# eLight_pro.net
KiCad netlist of a schematic drawn in EasyEDA Pro
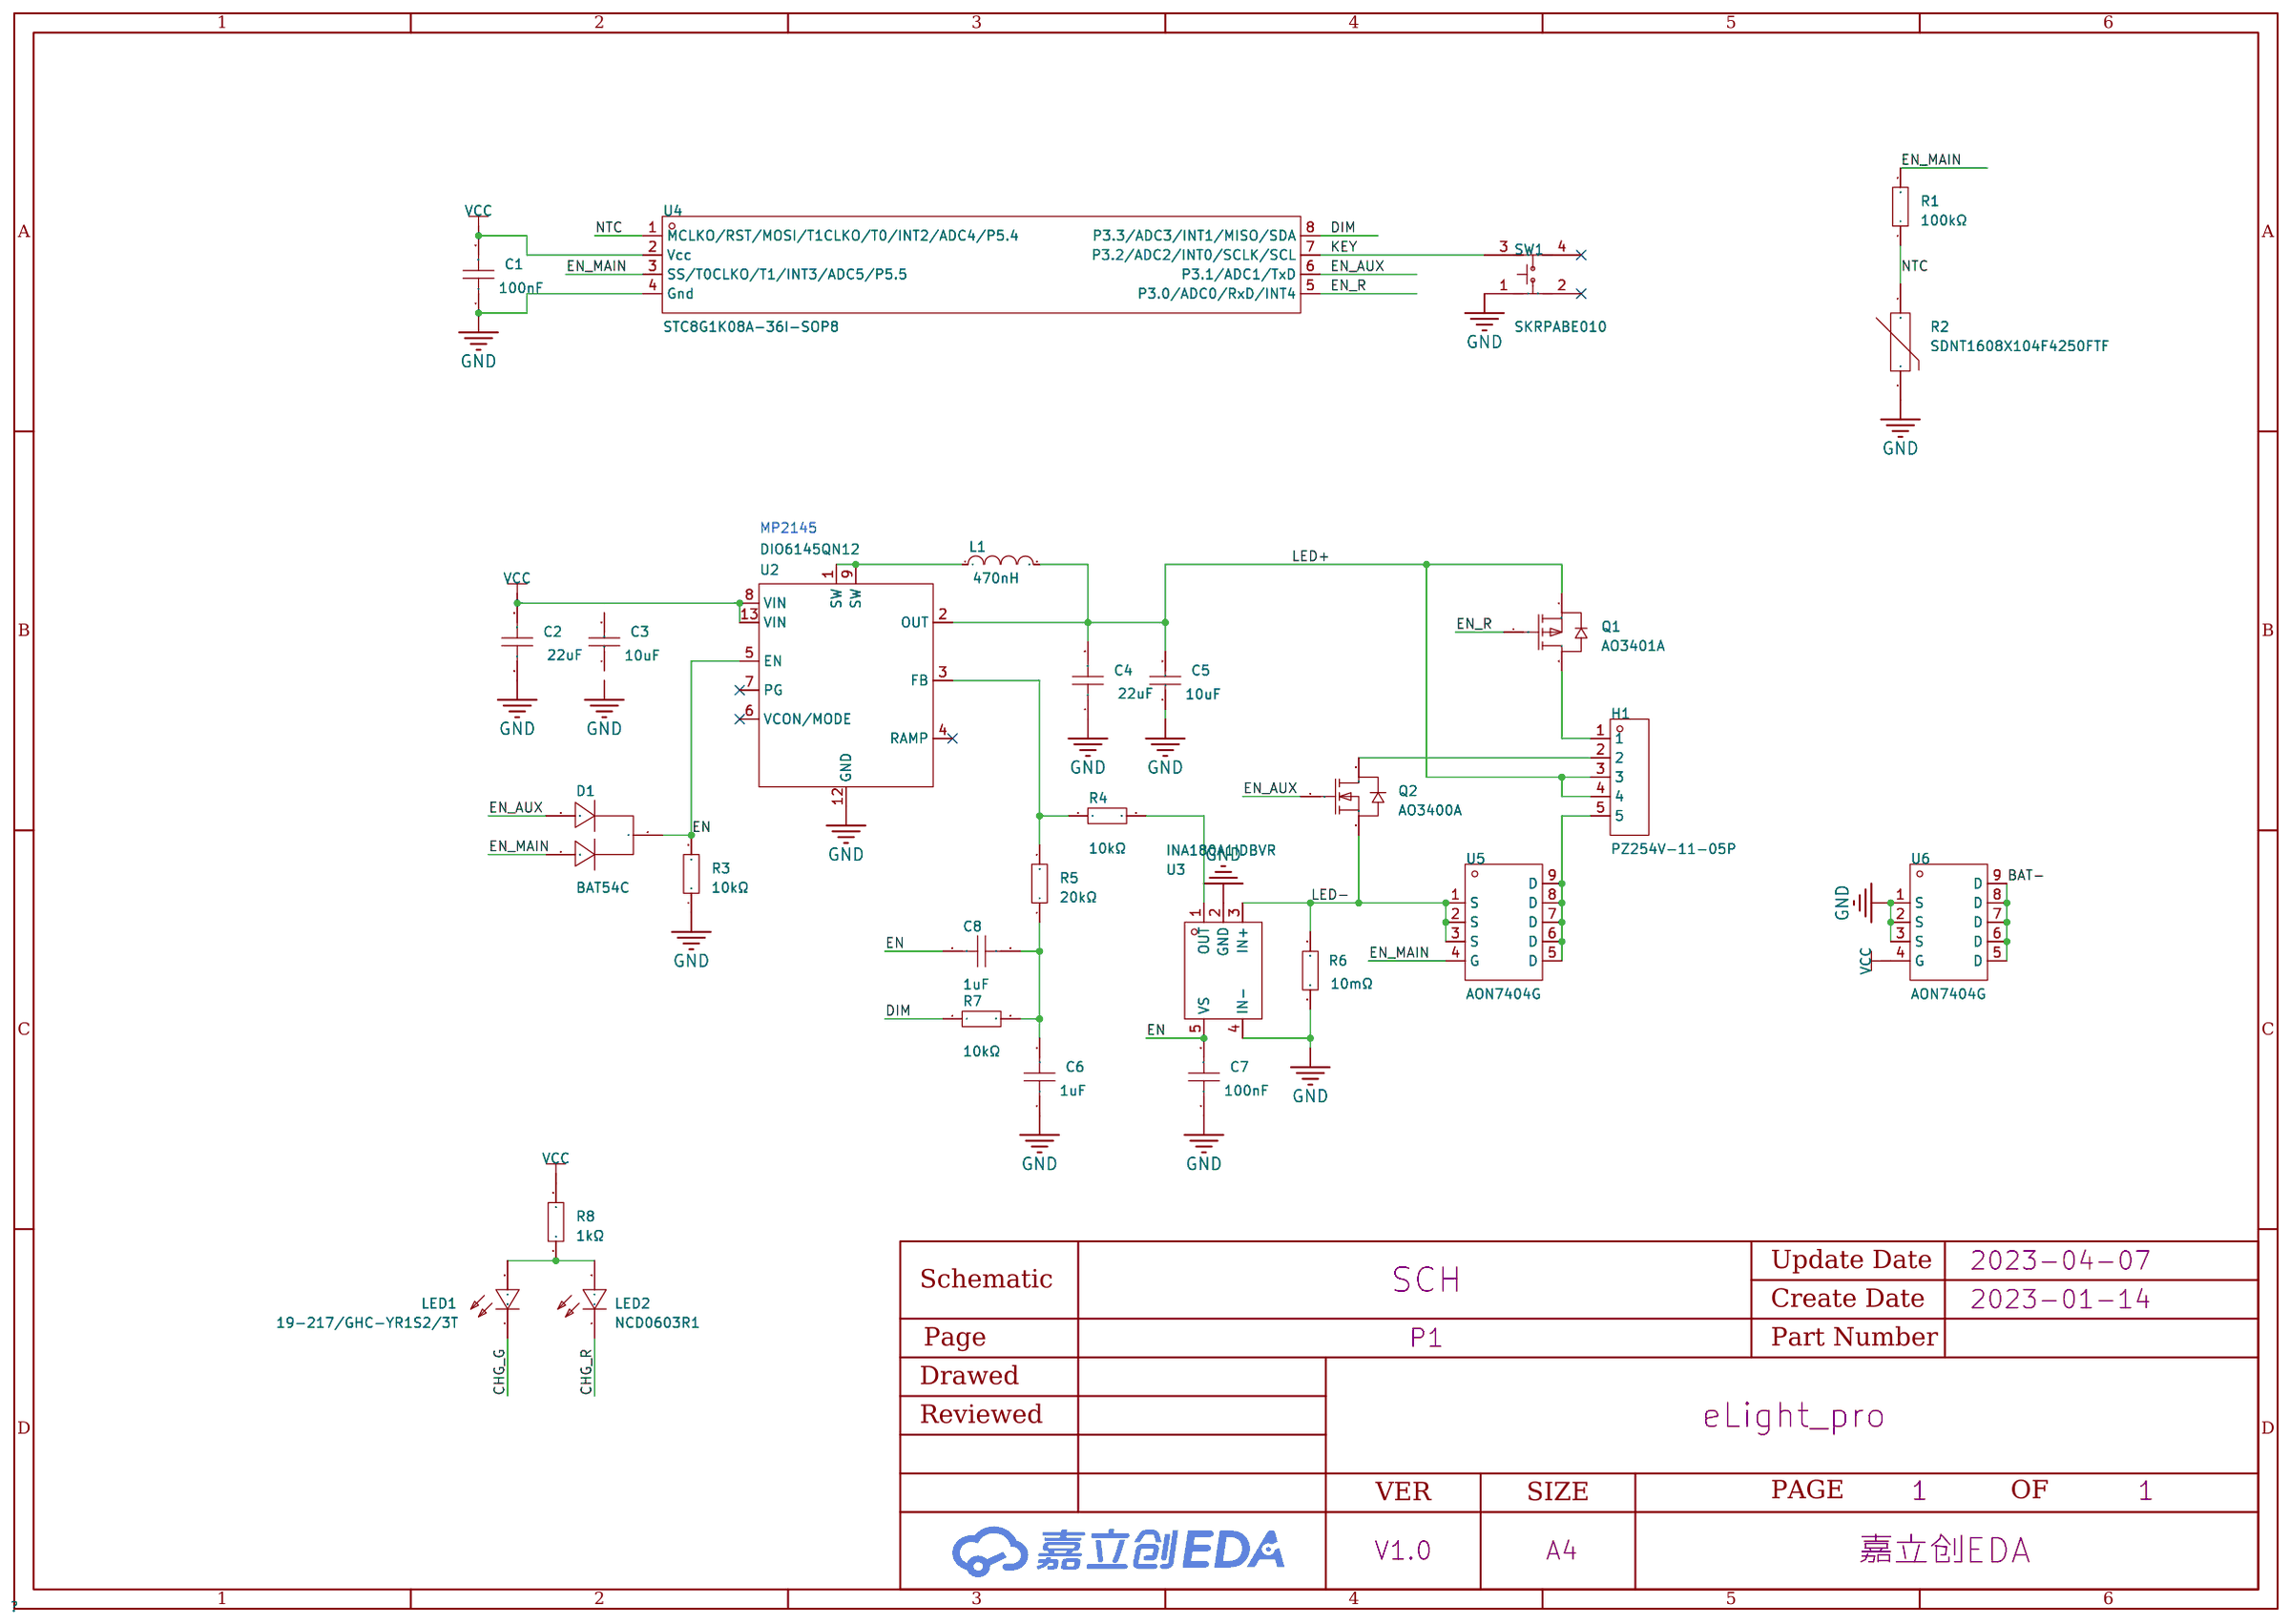
[diagram p0: schematic sheet]

(export (version "E")
  (design (tool "Eeschema 10.0.6"))
  (components
    (comp (ref "C1")
      (value "100nF")
      (footprint "easyedapro:C0603")
      (description "容值:100nF;精度:±10%;额定电压:50V;材质(温度系数):X7R;")
      (fields
        (field (name "Manufacturer Part") "CC0603KRX7R9BB104")
        (field (name "Manufacturer") "YAGEO(国巨)")
      )
      (libsource (lib "easyedapro") (part "CC0603KRX7R9BB104"))
    )
    (comp (ref "C2")
      (value "22uF")
      (footprint "easyedapro:C0805")
      (description "容值:22uF;精度:±20%;额定电压:25V;材质(温度系数):X5R;")
      (fields
        (field (name "Manufacturer Part") "CL21A226MAQNNNE")
        (field (name "Manufacturer") "SAMSUNG(三星)")
      )
      (libsource (lib "easyedapro") (part "CL21A226MAQNNNE"))
    )
    (comp (ref "C3")
      (value "10uF")
      (footprint "easyedapro:C0603")
      (description "容值:1uF;精度:±10%;额定电压:50V;材质(温度系数):X5R;")
      (fields
        (field (name "Manufacturer Part") "CL10A106KP8NNNC")
        (field (name "Manufacturer") "SAMSUNG(三星)")
      )
      (libsource (lib "easyedapro") (part "CL10A105KB8NNNC"))
    )
    (comp (ref "C4")
      (value "22uF")
      (footprint "easyedapro:C0805")
      (description "容值:22uF;精度:±20%;额定电压:25V;材质(温度系数):X5R;")
      (fields
        (field (name "Manufacturer Part") "CL21A226MAQNNNE")
        (field (name "Manufacturer") "SAMSUNG(三星)")
      )
      (libsource (lib "easyedapro") (part "CL21A226MAQNNNE"))
    )
    (comp (ref "C5")
      (value "10uF")
      (footprint "easyedapro:C0603")
      (description "容值:1uF;精度:±10%;额定电压:50V;材质(温度系数):X5R;")
      (fields
        (field (name "Manufacturer Part") "CL10A106KP8NNNC")
        (field (name "Manufacturer") "SAMSUNG(三星)")
      )
      (libsource (lib "easyedapro") (part "CL10A105KB8NNNC"))
    )
    (comp (ref "C6")
      (value "1uF")
      (footprint "easyedapro:C0603")
      (description "温度系数:X5R;精度:±10%;额定电压:50V;容值:1uF;")
      (fields
        (field (name "Manufacturer Part") "CL10A105KB8NNNC")
        (field (name "Manufacturer") "SAMSUNG(三星)")
      )
      (libsource (lib "easyedapro") (part "CL10A106KP8NNNC"))
    )
    (comp (ref "C7")
      (value "100nF")
      (footprint "easyedapro:C0603")
      (description "容值:100nF;精度:±10%;额定电压:50V;材质(温度系数):X7R;")
      (fields
        (field (name "Manufacturer Part") "CC0603KRX7R9BB104")
        (field (name "Manufacturer") "YAGEO(国巨)")
      )
      (libsource (lib "easyedapro") (part "CC0603KRX7R9BB104"))
    )
    (comp (ref "C8")
      (value "1uF")
      (footprint "easyedapro:C0603")
      (description "温度系数:X5R;精度:±10%;额定电压:50V;容值:1uF;")
      (fields
        (field (name "Manufacturer Part") "CL10A105KB8NNNC")
        (field (name "Manufacturer") "SAMSUNG(三星)")
      )
      (libsource (lib "easyedapro") (part "CL10A106KP8NNNC"))
    )
    (comp (ref "D1")
      (value "BAT54C")
      (footprint "easyedapro:SOT-23-3_L2.9-W1.6-P1.90-LS2.8-BR")
      (description "二极管配置:-;直流反向耐压(Vr):30V;平均整流电流(Io):200mA;正向压降(Vf):1V@100mA;反向电流(Ir):-;")
      (fields (field (name "Manufacturer") "CJ(江苏长电/长晶)"))
      (libsource (lib "easyedapro") (part "BAT54C"))
    )
    (comp (ref "H1")
      (value "PZ254V-11-05P")
      (footprint "easyedapro:HDR-TH_5P-P2.54-V-M")
      (fields (field (name "Manufacturer") "XFCN(兴飞)"))
      (libsource (lib "easyedapro") (part "PZ254V-11-05P"))
    )
    (comp (ref "L1")
      (value "470nH")
      (footprint "easyedapro:IND-SMD_L4.5-W4.0-1")
      (description "电感值:2.2uH;精度:±20%;额定电流:3A;直流电阻(DCR):52mΩ;")
      (fields (field (name "Manufacturer Part") "FXL0420-R47-M") (field (name "Manufacturer") "cjiang(长江微电)"))
      (libsource (lib "easyedapro") (part "MCS0420-2R2MN2"))
    )
    (comp (ref "LED1")
      (value "19-217/GHC-YR1S2/3T")
      (footprint "easyedapro:LED0603-RD")
      (fields (field (name "Manufacturer") "EVERLIGHT(亿光)"))
      (libsource (lib "easyedapro") (part "19-217/GHC-YR1S2/3T"))
    )
    (comp (ref "LED2")
      (value "NCD0603R1")
      (footprint "easyedapro:LED0603-RD_RED")
      (description "发光颜色:红灯;")
      (fields (field (name "Manufacturer") "国星光电"))
      (libsource (lib "easyedapro") (part "FC-DA1608HRK-620D"))
    )
    (comp (ref "Q1")
      (value "AO3401A")
      (footprint "easyedapro:SOT-23_L2.9-W1.3-P1.90-LS2.4-BR")
      (fields (field (name "Manufacturer") "AOS"))
      (libsource (lib "easyedapro") (part "AO3401A"))
    )
    (comp (ref "Q2")
      (value "AO3400A")
      (footprint "easyedapro:SOT-23-3_L2.9-W1.6-P1.90-LS2.8-BR")
      (fields (field (name "Manufacturer") "AOS"))
      (libsource (lib "easyedapro") (part "AO3400A"))
    )
    (comp (ref "R1")
      (value "100kΩ")
      (footprint "easyedapro:R0603")
      (description "电阻类型:厚膜电阻;阻值:10kΩ;精度:±1%;功率:100mW;温度系数:±100ppm/°C;最大工作电压:75V;工作温度范围:-55°C~+155°C;")
      (fields
        (field (name "Manufacturer Part") "0603WAF1003T5E")
        (field (name "Manufacturer") "UNI-ROYAL(厚声)")
      )
      (libsource (lib "easyedapro") (part "0603WAF1002T5E"))
    )
    (comp (ref "R2")
      (value "SDNT1608X104F4250FTF")
      (footprint "easyedapro:R0603")
      (fields (field (name "Manufacturer") "Sunlord(顺络)"))
      (libsource (lib "easyedapro") (part "SDNT1608X103F3950FTF"))
    )
    (comp (ref "R3")
      (value "10kΩ")
      (footprint "easyedapro:R0603")
      (description "电阻类型:厚膜电阻;阻值:100kΩ;精度:±1%;功率:100mW;温度系数:±100ppm/°C;最大工作电压:75V;工作温度范围:-55°C~+155°C;")
      (fields
        (field (name "Manufacturer Part") "0603WAF1002T5E")
        (field (name "Manufacturer") "UNI-ROYAL(厚声)")
      )
      (libsource (lib "easyedapro") (part "0603WAF1003T5E"))
    )
    (comp (ref "R4")
      (value "10kΩ")
      (footprint "easyedapro:R0603")
      (description "电阻类型:厚膜电阻;阻值:100kΩ;精度:±1%;功率:100mW;温度系数:±100ppm/°C;最大工作电压:75V;工作温度范围:-55°C~+155°C;")
      (fields
        (field (name "Manufacturer Part") "0603WAF1002T5E")
        (field (name "Manufacturer") "UNI-ROYAL(厚声)")
      )
      (libsource (lib "easyedapro") (part "0603WAF1003T5E"))
    )
    (comp (ref "R5")
      (value "20kΩ")
      (footprint "easyedapro:R0603")
      (description "电阻类型:厚膜电阻;阻值:100kΩ;精度:±1%;功率:100mW;温度系数:±100ppm/°C;最大工作电压:75V;工作温度范围:-55°C~+155°C;")
      (fields
        (field (name "Manufacturer Part") "0603WAF2002T5E")
        (field (name "Manufacturer") "UNI-ROYAL(厚声)")
      )
      (libsource (lib "easyedapro") (part "0603WAF1003T5E"))
    )
    (comp (ref "R6")
      (value "10mΩ")
      (footprint "easyedapro:R1206")
      (description "阻值:10mΩ;精度:±1%;功率:1W;温度系数:±70ppm/°C;")
      (fields (field (name "Manufacturer Part") "FMF06FTHR010-LH") (field (name "Manufacturer") "PSA(信昌电陶)"))
      (libsource (lib "easyedapro") (part "FMF06FTHR010-LHL"))
    )
    (comp (ref "R7")
      (value "10kΩ")
      (footprint "easyedapro:R0603")
      (description "电阻类型:厚膜电阻;阻值:100kΩ;精度:±1%;功率:100mW;温度系数:±100ppm/°C;最大工作电压:75V;工作温度范围:-55°C~+155°C;")
      (fields
        (field (name "Manufacturer Part") "0603WAF1002T5E")
        (field (name "Manufacturer") "UNI-ROYAL(厚声)")
      )
      (libsource (lib "easyedapro") (part "0603WAF1003T5E"))
    )
    (comp (ref "R8")
      (value "1kΩ")
      (footprint "easyedapro:R0603")
      (description "电阻类型:厚膜电阻;阻值:1kΩ;精度:±1%;功率:100mW;温度系数:±100ppm/°C;最大工作电压:75V;工作温度范围:-55°C~+155°C;")
      (fields
        (field (name "Manufacturer Part") "0603WAF1001T5E")
        (field (name "Manufacturer") "UNI-ROYAL(厚声)")
      )
      (libsource (lib "easyedapro") (part "0603WAF1001T5E"))
    )
    (comp (ref "SW1")
      (value "SKRPABE010")
      (footprint "easyedapro:KEY-SMD_4P-L4.2-W3.2-P2.20-LS4.6")
      (description "触点电流:50mA;额定电压(DC):16V;电路结构:单刀单掷;按钮作用方向:顶部触动;致动器样式:椭圆形按钮;照明颜色:-;开关长度:4.2mm;开关宽度:3.2mm;开关高度:2.5mm;")
      (fields (field (name "Manufacturer") "ALPSALPINE(阿尔卑斯阿尔派)"))
      (libsource (lib "easyedapro") (part "SKRPABE010"))
    )
    (comp (ref "U2")
      (value "DIO6145QN12")
      (footprint "easyedapro:QFN-12_L3.0-W2.0-P0.50_DIO6145QN12")
      (fields (field (name "Manufacturer") "DIOO(帝奥微)"))
      (libsource (lib "easyedapro") (part "DIO6145QN12"))
    )
    (comp (ref "U3")
      (value "INA180A1IDBVR")
      (footprint "easyedapro:SOT-23-5_L3.0-W1.7-P0.95-LS2.8-BR")
      (description "INA180 INA180 多通道电流感应放大器")
      (fields (field (name "Manufacturer") "TI(德州仪器)"))
      (libsource (lib "easyedapro") (part "INA180A1IDBVR"))
    )
    (comp (ref "U4")
      (value "STC8G1K08A-36I-SOP8")
      (footprint "easyedapro:SOP-8_L5.0-W4.0-P1.27-LS6.0-BL")
      (fields (field (name "Manufacturer") "STC(宏晶)"))
      (libsource (lib "easyedapro") (part "STC8G1K08A-36I-SOP8"))
    )
    (comp (ref "U5")
      (value "AON7404G")
      (footprint "easyedapro:DFN-8_L3.0-W3.0-P0.65-BL-2")
      (fields (field (name "Manufacturer") "AOS"))
      (libsource (lib "easyedapro") (part "AON7404G"))
    )
    (comp (ref "U6")
      (value "AON7404G")
      (footprint "easyedapro:DFN-8_L3.0-W3.0-P0.65-BL-2")
      (fields (field (name "Manufacturer") "AOS"))
      (libsource (lib "easyedapro") (part "AON7404G"))
    )
  )
  (nets
    (net (code "1") (name "/BAT-") (class "Default")
      (node (ref "U6") (pin "5") (pinfunction "D_5") (pintype "input"))
      (node (ref "U6") (pin "6") (pinfunction "D_6") (pintype "input"))
      (node (ref "U6") (pin "7") (pinfunction "D_7") (pintype "input"))
      (node (ref "U6") (pin "8") (pinfunction "D_8") (pintype "input"))
      (node (ref "U6") (pin "9") (pinfunction "D_9") (pintype "input"))
    )
    (net (code "2") (name "/CHG_G") (class "Default")
      (node (ref "LED1") (pin "1") (pinfunction "C_1") (pintype "input"))
    )
    (net (code "3") (name "/CHG_R") (class "Default")
      (node (ref "LED2") (pin "1") (pinfunction "K_1") (pintype "input"))
    )
    (net (code "4") (name "/DIM") (class "Default")
      (node (ref "R7") (pin "1") (pinfunction "1_1") (pintype "input"))
      (node (ref "U4") (pin "8") (pinfunction "P3.3/ADC3/INT1/MISO/SDA_8") (pintype "input"))
    )
    (net (code "5") (name "/EN") (class "Default")
      (node (ref "C7") (pin "2") (pinfunction "2_2") (pintype "input"))
      (node (ref "C8") (pin "2") (pinfunction "2_2") (pintype "input"))
      (node (ref "D1") (pin "3") (pinfunction "K_3") (pintype "input"))
      (node (ref "R3") (pin "2") (pinfunction "2_2") (pintype "input"))
      (node (ref "U2") (pin "5") (pinfunction "EN_5") (pintype "input"))
      (node (ref "U3") (pin "5") (pinfunction "VS_5") (pintype "input"))
    )
    (net (code "6") (name "/EN_AUX") (class "Default")
      (node (ref "D1") (pin "1") (pinfunction "A1_1") (pintype "input"))
      (node (ref "Q2") (pin "1") (pinfunction "G_1") (pintype "input"))
      (node (ref "U4") (pin "6") (pinfunction "P3.1/ADC1/TxD_6") (pintype "input"))
    )
    (net (code "7") (name "/EN_MAIN") (class "Default")
      (node (ref "D1") (pin "2") (pinfunction "A2_2") (pintype "input"))
      (node (ref "R1") (pin "2") (pinfunction "2_2") (pintype "input"))
      (node (ref "U4") (pin "3") (pinfunction "SS/T0CLKO/T1/INT3/ADC5/P5.5_3") (pintype "input"))
      (node (ref "U5") (pin "4") (pinfunction "G_4") (pintype "input"))
    )
    (net (code "8") (name "/EN_R") (class "Default")
      (node (ref "Q1") (pin "1") (pinfunction "G_1") (pintype "input"))
      (node (ref "U4") (pin "5") (pinfunction "P3.0/ADC0/RxD/INT4_5") (pintype "input"))
    )
    (net (code "9") (name "/KEY") (class "Default")
      (node (ref "SW1") (pin "3") (pinfunction "3_3") (pintype "input"))
      (node (ref "U4") (pin "7") (pinfunction "P3.2/ADC2/INT0/SCLK/SCL_7") (pintype "input"))
    )
    (net (code "10") (name "/LED+") (class "Default")
      (node (ref "C4") (pin "2") (pinfunction "2_2") (pintype "input"))
      (node (ref "C5") (pin "2") (pinfunction "2_2") (pintype "input"))
      (node (ref "H1") (pin "3") (pinfunction "3_3") (pintype "input"))
      (node (ref "H1") (pin "4") (pinfunction "4_4") (pintype "input"))
      (node (ref "L1") (pin "2") (pinfunction "2_2") (pintype "input"))
      (node (ref "Q1") (pin "2") (pinfunction "S_2") (pintype "input"))
      (node (ref "U2") (pin "2") (pinfunction "OUT_2") (pintype "input"))
    )
    (net (code "11") (name "/LED-") (class "Default")
      (node (ref "Q2") (pin "2") (pinfunction "S_2") (pintype "input"))
      (node (ref "R6") (pin "2") (pinfunction "2_2") (pintype "input"))
      (node (ref "U3") (pin "3") (pinfunction "IN+_3") (pintype "input"))
      (node (ref "U5") (pin "1") (pinfunction "S_1") (pintype "input"))
      (node (ref "U5") (pin "2") (pinfunction "S_2") (pintype "input"))
      (node (ref "U5") (pin "3") (pinfunction "S_3") (pintype "input"))
    )
    (net (code "12") (name "/NTC") (class "Default")
      (node (ref "R1") (pin "1") (pinfunction "1_1") (pintype "input"))
      (node (ref "R2") (pin "2") (pinfunction "2_2") (pintype "input"))
      (node (ref "U4") (pin "1") (pinfunction "MCLKO/RST/MOSI/T1CLKO/T0/INT2/ADC4/P5.4_1") (pintype "input"))
    )
    (net (code "13") (name "GND") (class "Default")
      (node (ref "C1") (pin "1") (pinfunction "1_1") (pintype "input"))
      (node (ref "C2") (pin "1") (pinfunction "1_1") (pintype "input"))
      (node (ref "C4") (pin "1") (pinfunction "1_1") (pintype "input"))
      (node (ref "C5") (pin "1") (pinfunction "1_1") (pintype "input"))
      (node (ref "C6") (pin "1") (pinfunction "1_1") (pintype "input"))
      (node (ref "C7") (pin "1") (pinfunction "1_1") (pintype "input"))
      (node (ref "R2") (pin "1") (pinfunction "1_1") (pintype "input"))
      (node (ref "R3") (pin "1") (pinfunction "1_1") (pintype "input"))
      (node (ref "R6") (pin "1") (pinfunction "1_1") (pintype "input"))
      (node (ref "SW1") (pin "1") (pinfunction "1_1") (pintype "input"))
      (node (ref "U2") (pin "12") (pinfunction "GND_12") (pintype "input"))
      (node (ref "U3") (pin "2") (pinfunction "GND_2") (pintype "input"))
      (node (ref "U3") (pin "4") (pinfunction "IN-_4") (pintype "input"))
      (node (ref "U4") (pin "4") (pinfunction "Gnd_4") (pintype "input"))
      (node (ref "U6") (pin "1") (pinfunction "S_1") (pintype "input"))
      (node (ref "U6") (pin "2") (pinfunction "S_2") (pintype "input"))
      (node (ref "U6") (pin "3") (pinfunction "S_3") (pintype "input"))
    )
    (net (code "14") (name "Net-(C6-Pad2)") (class "Default")
      (node (ref "C6") (pin "2") (pinfunction "2_2") (pintype "input"))
      (node (ref "C8") (pin "1") (pinfunction "1_1") (pintype "input"))
      (node (ref "R5") (pin "1") (pinfunction "1_1") (pintype "input"))
      (node (ref "R7") (pin "2") (pinfunction "2_2") (pintype "input"))
    )
    (net (code "15") (name "Net-(H1-Pad5)") (class "Default")
      (node (ref "H1") (pin "5") (pinfunction "5_5") (pintype "input"))
      (node (ref "U5") (pin "5") (pinfunction "D_5") (pintype "input"))
      (node (ref "U5") (pin "6") (pinfunction "D_6") (pintype "input"))
      (node (ref "U5") (pin "7") (pinfunction "D_7") (pintype "input"))
      (node (ref "U5") (pin "8") (pinfunction "D_8") (pintype "input"))
      (node (ref "U5") (pin "9") (pinfunction "D_9") (pintype "input"))
    )
    (net (code "16") (name "Net-(L1-Pad1)") (class "Default")
      (node (ref "L1") (pin "1") (pinfunction "1_1") (pintype "input"))
      (node (ref "U2") (pin "1") (pinfunction "SW_1") (pintype "input"))
      (node (ref "U2") (pin "9") (pinfunction "SW_9") (pintype "input"))
    )
    (net (code "17") (name "Net-(LED1-A)") (class "Default")
      (node (ref "LED1") (pin "2") (pinfunction "A_2") (pintype "input"))
      (node (ref "LED2") (pin "2") (pinfunction "A_2") (pintype "input"))
      (node (ref "R8") (pin "1") (pinfunction "1_1") (pintype "input"))
    )
    (net (code "18") (name "Net-(Q1-D)") (class "Default")
      (node (ref "H1") (pin "1") (pinfunction "1_1") (pintype "input"))
      (node (ref "Q1") (pin "3") (pinfunction "D_3") (pintype "input"))
    )
    (net (code "19") (name "Net-(Q2-D)") (class "Default")
      (node (ref "H1") (pin "2") (pinfunction "2_2") (pintype "input"))
      (node (ref "Q2") (pin "3") (pinfunction "D_3") (pintype "input"))
    )
    (net (code "20") (name "Net-(U2-FB)") (class "Default")
      (node (ref "R4") (pin "1") (pinfunction "1_1") (pintype "input"))
      (node (ref "R5") (pin "2") (pinfunction "2_2") (pintype "input"))
      (node (ref "U2") (pin "3") (pinfunction "FB_3") (pintype "input"))
    )
    (net (code "21") (name "Net-(U3-OUT)") (class "Default")
      (node (ref "R4") (pin "2") (pinfunction "2_2") (pintype "input"))
      (node (ref "U3") (pin "1") (pinfunction "OUT_1") (pintype "input"))
    )
    (net (code "22") (name "VCC") (class "Default")
      (node (ref "C1") (pin "2") (pinfunction "2_2") (pintype "input"))
      (node (ref "C2") (pin "2") (pinfunction "2_2") (pintype "input"))
      (node (ref "R8") (pin "2") (pinfunction "2_2") (pintype "input"))
      (node (ref "U2") (pin "13") (pinfunction "VIN_13") (pintype "input"))
      (node (ref "U2") (pin "8") (pinfunction "VIN_8") (pintype "input"))
      (node (ref "U4") (pin "2") (pinfunction "Vcc_2") (pintype "input"))
      (node (ref "U6") (pin "4") (pinfunction "G_4") (pintype "input"))
    )
    (net (code "23") (name "unconnected-(C3-Pad1)") (class "Default")
      (node (ref "C3") (pin "1") (pinfunction "1_1") (pintype "input"))
    )
    (net (code "24") (name "unconnected-(C3-Pad2)") (class "Default")
      (node (ref "C3") (pin "2") (pinfunction "2_2") (pintype "input"))
    )
    (net (code "25") (name "unconnected-(SW1-Pad2)") (class "Default")
      (node (ref "SW1") (pin "2") (pinfunction "2_2") (pintype "input+no_connect"))
    )
    (net (code "26") (name "unconnected-(SW1-Pad4)") (class "Default")
      (node (ref "SW1") (pin "4") (pinfunction "4_4") (pintype "input+no_connect"))
    )
    (net (code "27") (name "unconnected-(U2-PG-Pad7)") (class "Default")
      (node (ref "U2") (pin "7") (pinfunction "PG_7") (pintype "input+no_connect"))
    )
    (net (code "28") (name "unconnected-(U2-RAMP-Pad4)") (class "Default")
      (node (ref "U2") (pin "4") (pinfunction "RAMP_4") (pintype "input+no_connect"))
    )
    (net (code "29") (name "unconnected-(U2-VCON{slash}MODE-Pad6)") (class "Default")
      (node (ref "U2") (pin "6") (pinfunction "VCON/MODE_6") (pintype "input+no_connect"))
    )
  )
)
